# H3_HMI_PulsadorSmall_A_Rev_1.net
KiCad netlist of a schematic drawn in EAGLE
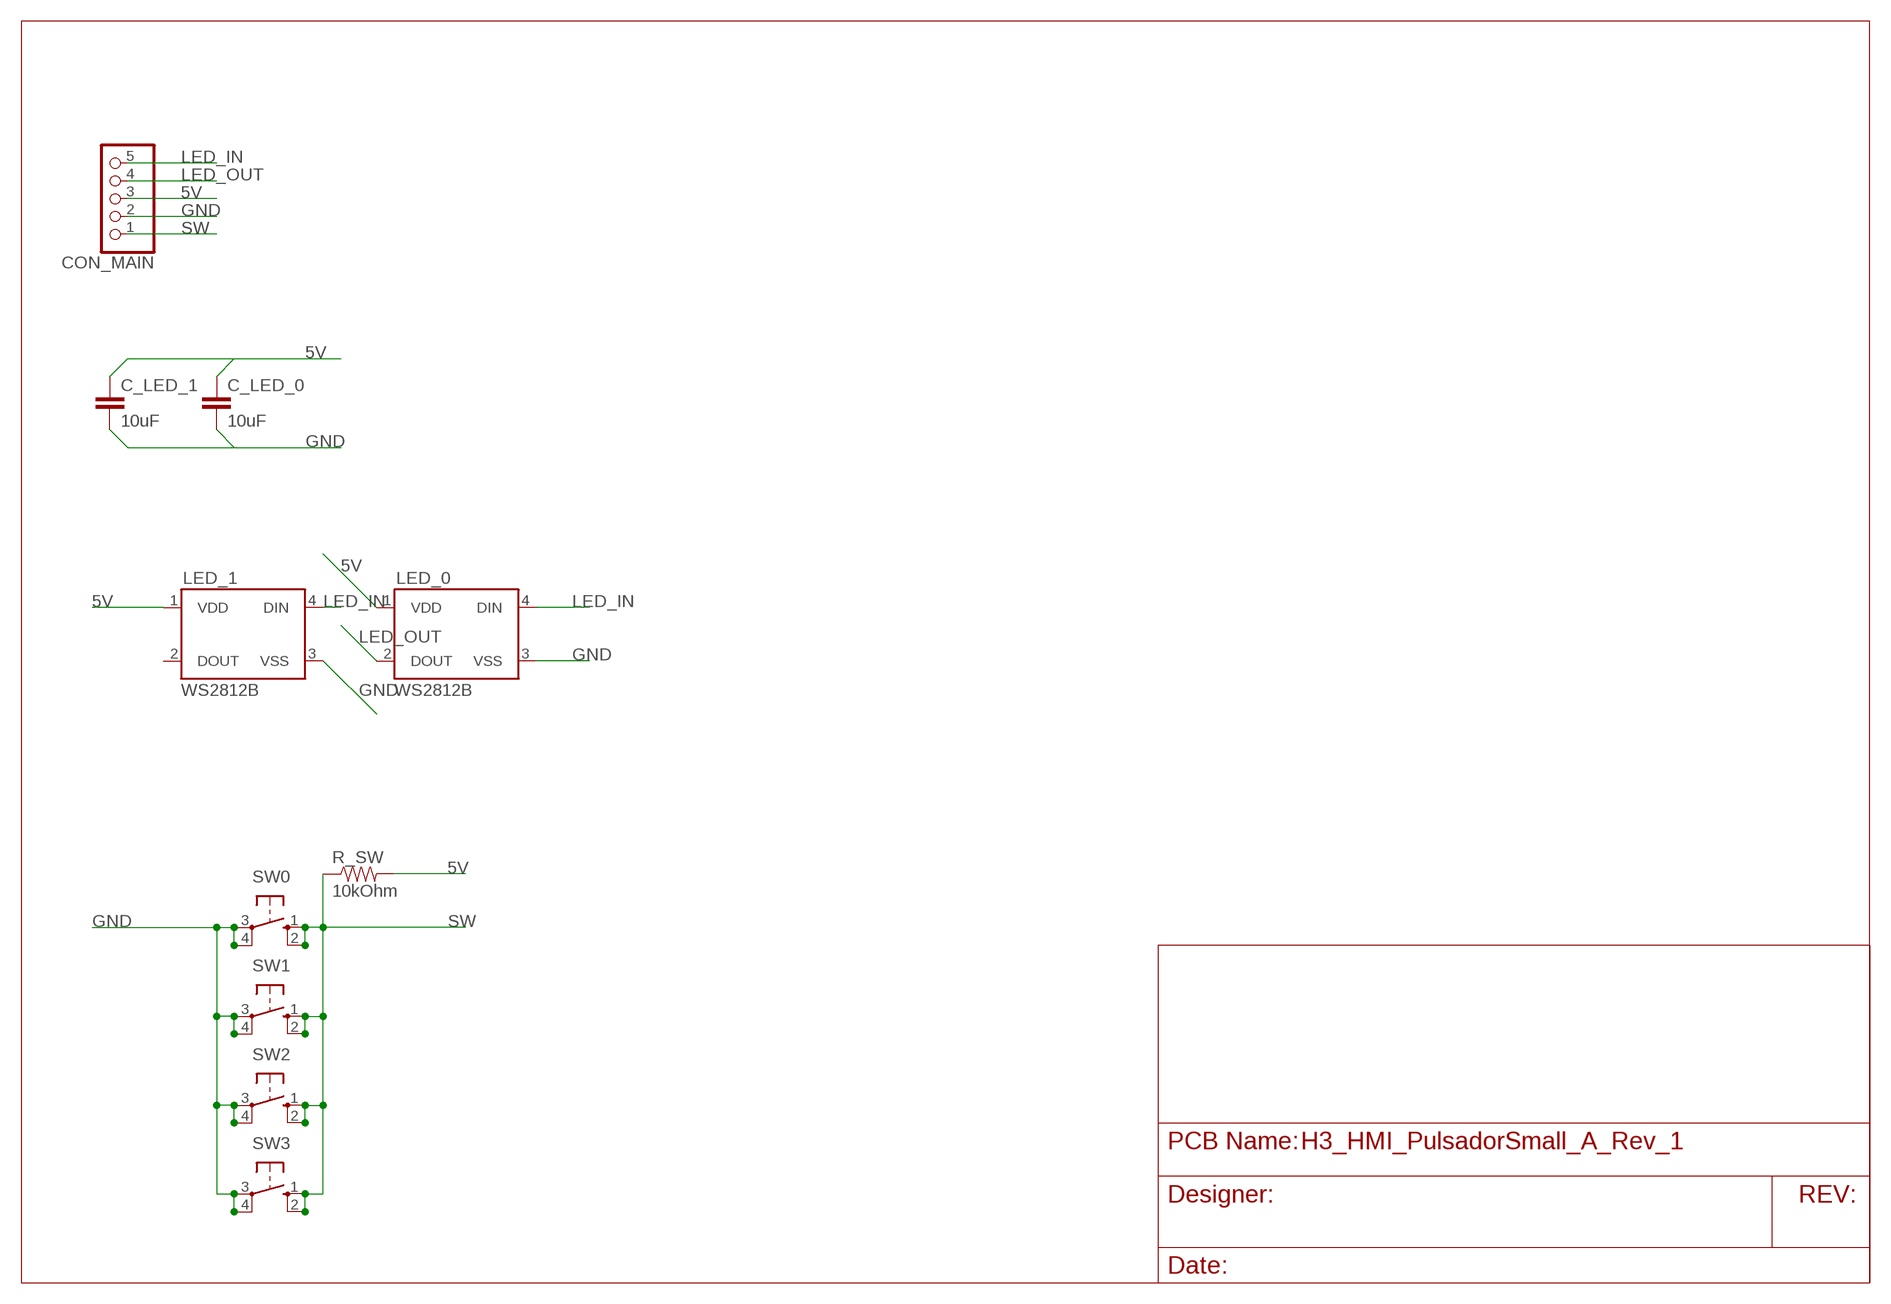
[diagram p0: schematic, sheet 1]

(export (version "E")
  (design (tool "Eeschema 10.0.6"))
  (components
    (comp (ref "CON_MAIN")
      (value "PINHD-1X5/90")
      (footprint "eagle-import:1X05_90")
      (libsource (lib "eagle-import") (part "PINHD-1X5/90"))
    )
    (comp (ref "C_LED_0")
      (value "10uF")
      (footprint "eagle-import:C1206")
      (libsource (lib "eagle-import") (part "C-EUC1206"))
    )
    (comp (ref "C_LED_1")
      (value "10uF")
      (footprint "eagle-import:C1206")
      (libsource (lib "eagle-import") (part "C-EUC1206"))
    )
    (comp (ref "LED_0")
      (value "WS2812B")
      (footprint "eagle-import:WS2812B")
      (libsource (lib "eagle-import") (part "WS2812B"))
    )
    (comp (ref "LED_1")
      (value "WS2812B")
      (footprint "eagle-import:WS2812B")
      (libsource (lib "eagle-import") (part "WS2812B"))
    )
    (comp (ref "R_SW")
      (value "10kOhm")
      (footprint "eagle-import:1206")
      (libsource (lib "eagle-import") (part "RESISTOR1206"))
    )
    (comp (ref "SW0")
      (value "10-XX")
      (footprint "eagle-import:B3F-10XX")
      (fields (field (name "MPN") "B3F-1000"))
      (libsource (lib "eagle-import") (part "10-XX"))
    )
    (comp (ref "SW1")
      (value "10-XX")
      (footprint "eagle-import:B3F-10XX")
      (fields (field (name "MPN") "B3F-1000"))
      (libsource (lib "eagle-import") (part "10-XX"))
    )
    (comp (ref "SW2")
      (value "10-XX")
      (footprint "eagle-import:B3F-10XX")
      (fields (field (name "MPN") "B3F-1000"))
      (libsource (lib "eagle-import") (part "10-XX"))
    )
    (comp (ref "SW3")
      (value "10-XX")
      (footprint "eagle-import:B3F-10XX")
      (fields (field (name "MPN") "B3F-1000"))
      (libsource (lib "eagle-import") (part "10-XX"))
    )
  )
  (nets
    (net (code "1") (name "/5V") (class "Default")
      (node (ref "CON_MAIN") (pin "3") (pinfunction "3_3") (pintype "passive"))
      (node (ref "C_LED_0") (pin "1") (pinfunction "1_1") (pintype "passive"))
      (node (ref "C_LED_1") (pin "1") (pinfunction "1_1") (pintype "passive"))
      (node (ref "LED_0") (pin "1") (pinfunction "VDD_1") (pintype "power_in"))
      (node (ref "LED_1") (pin "1") (pinfunction "VDD_1") (pintype "power_in"))
      (node (ref "R_SW") (pin "2") (pinfunction "2_2") (pintype "passive"))
    )
    (net (code "2") (name "/GND") (class "Default")
      (node (ref "CON_MAIN") (pin "2") (pinfunction "2_2") (pintype "passive"))
      (node (ref "C_LED_0") (pin "2") (pinfunction "2_2") (pintype "passive"))
      (node (ref "C_LED_1") (pin "2") (pinfunction "2_2") (pintype "passive"))
      (node (ref "LED_0") (pin "3") (pinfunction "VSS_3") (pintype "power_in"))
      (node (ref "LED_1") (pin "3") (pinfunction "VSS_3") (pintype "power_in"))
      (node (ref "SW0") (pin "3") (pinfunction "P_3") (pintype "passive"))
      (node (ref "SW0") (pin "4") (pinfunction "P1_4") (pintype "passive"))
      (node (ref "SW1") (pin "3") (pinfunction "P_3") (pintype "passive"))
      (node (ref "SW1") (pin "4") (pinfunction "P1_4") (pintype "passive"))
      (node (ref "SW2") (pin "3") (pinfunction "P_3") (pintype "passive"))
      (node (ref "SW2") (pin "4") (pinfunction "P1_4") (pintype "passive"))
      (node (ref "SW3") (pin "3") (pinfunction "P_3") (pintype "passive"))
      (node (ref "SW3") (pin "4") (pinfunction "P1_4") (pintype "passive"))
    )
    (net (code "3") (name "/LED_IN") (class "Default")
      (node (ref "CON_MAIN") (pin "5") (pinfunction "5_5") (pintype "passive"))
      (node (ref "LED_0") (pin "4") (pinfunction "DIN_4") (pintype "input"))
      (node (ref "LED_1") (pin "4") (pinfunction "DIN_4") (pintype "input"))
    )
    (net (code "4") (name "/LED_OUT") (class "Default")
      (node (ref "CON_MAIN") (pin "4") (pinfunction "4_4") (pintype "passive"))
      (node (ref "LED_0") (pin "2") (pinfunction "DOUT_2") (pintype "output"))
    )
    (net (code "5") (name "/SW") (class "Default")
      (node (ref "CON_MAIN") (pin "1") (pinfunction "1_1") (pintype "passive"))
      (node (ref "R_SW") (pin "1") (pinfunction "1_1") (pintype "passive"))
      (node (ref "SW0") (pin "1") (pinfunction "S_1") (pintype "passive"))
      (node (ref "SW0") (pin "2") (pinfunction "S1_2") (pintype "passive"))
      (node (ref "SW1") (pin "1") (pinfunction "S_1") (pintype "passive"))
      (node (ref "SW1") (pin "2") (pinfunction "S1_2") (pintype "passive"))
      (node (ref "SW2") (pin "1") (pinfunction "S_1") (pintype "passive"))
      (node (ref "SW2") (pin "2") (pinfunction "S1_2") (pintype "passive"))
      (node (ref "SW3") (pin "1") (pinfunction "S_1") (pintype "passive"))
      (node (ref "SW3") (pin "2") (pinfunction "S1_2") (pintype "passive"))
    )
    (net (code "6") (name "unconnected-(LED_1-DOUT-Pad2)") (class "Default")
      (node (ref "LED_1") (pin "2") (pinfunction "DOUT_2") (pintype "output"))
    )
  )
)
